# BCK_REVA.net
KiCad netlist of a schematic drawn in Altium Designer
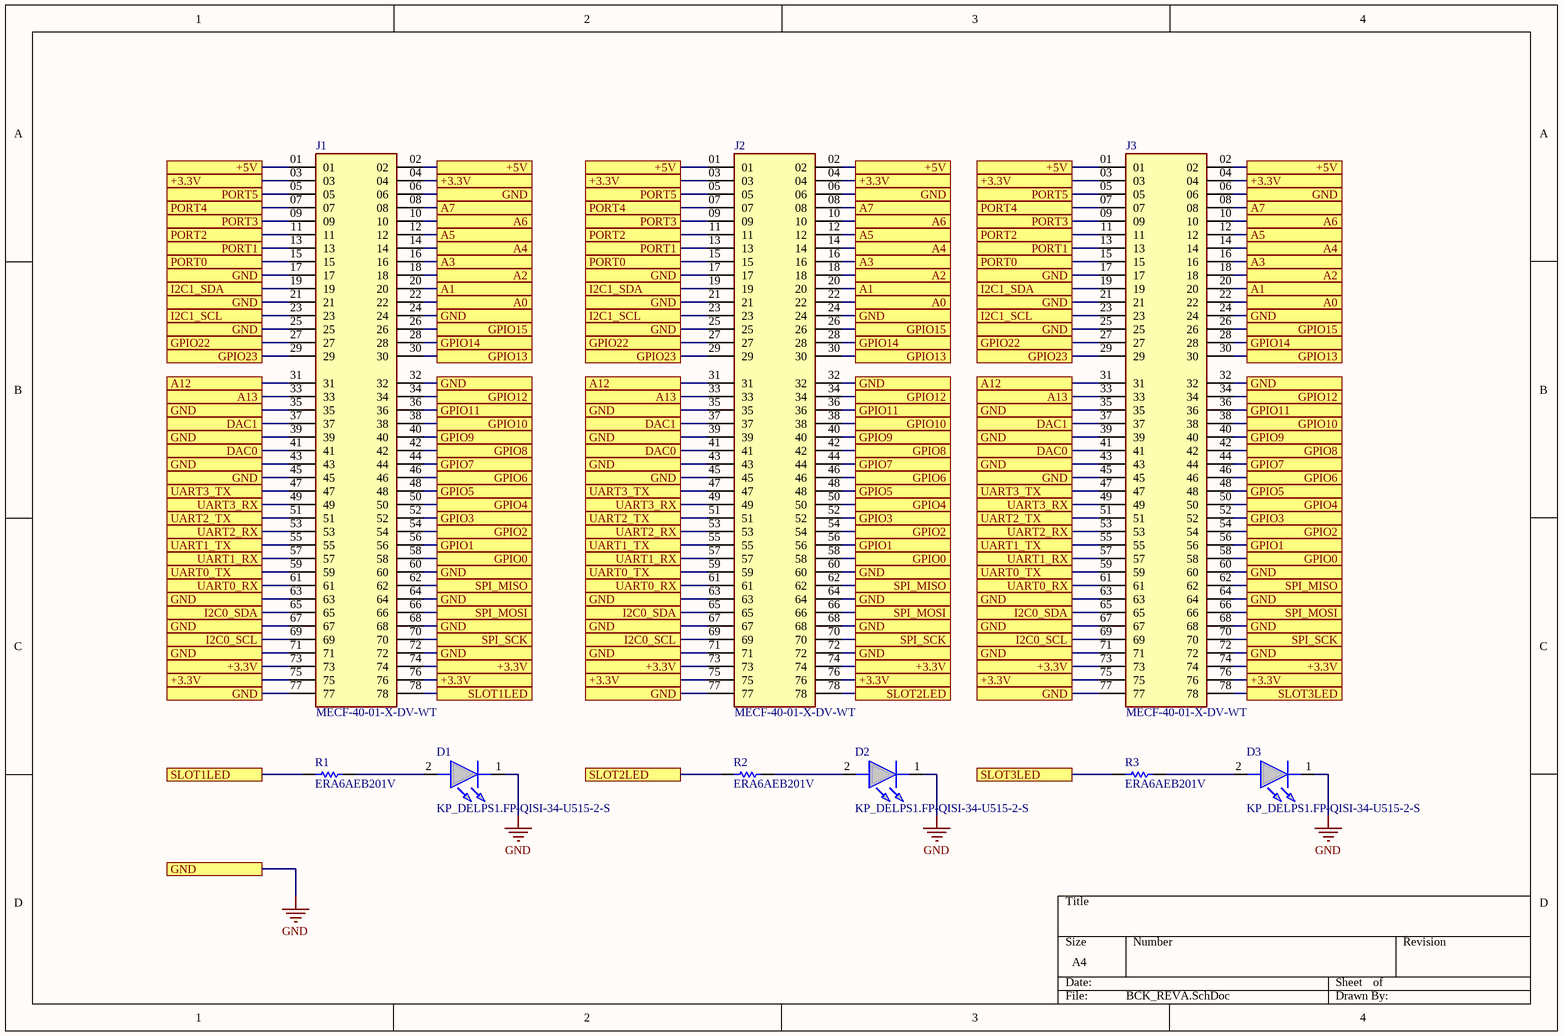
[diagram p0: BCK_REVA.SchDoc]

(export (version "E")
  (design (tool "Eeschema 10.0.6"))
  (components
    (comp (ref "D1")
      (value "KP_DELPS1.FP-QISI-34-U515-2-S")
      (footprint "KPDELPS1FPQISI34U5152S:KPDELPS1FPQISI34U5152S")
      (description "High Power LEDs - Single Color Pure Green TOPLED E1608")
      (fields
        (field (name "MANUFACTURER_PART_NUMBER") "KP DELPS1.FP-QISI-34-U515-2-S")
        (field (name "MOUSER PART NUMBER") "720-KPDELPS1FPA0817")
      )
      (libsource (lib "Backplane_REVA") (part "KP_DELPS1.FP-QISI-34-U515-2-S"))
    )
    (comp (ref "D2")
      (value "KP_DELPS1.FP-QISI-34-U515-2-S")
      (footprint "KPDELPS1FPQISI34U5152S:KPDELPS1FPQISI34U5152S")
      (description "High Power LEDs - Single Color Pure Green TOPLED E1608")
      (fields
        (field (name "MANUFACTURER_PART_NUMBER") "KP DELPS1.FP-QISI-34-U515-2-S")
        (field (name "MOUSER PART NUMBER") "720-KPDELPS1FPA0817")
      )
      (libsource (lib "Backplane_REVA") (part "KP_DELPS1.FP-QISI-34-U515-2-S"))
    )
    (comp (ref "D3")
      (value "KP_DELPS1.FP-QISI-34-U515-2-S")
      (footprint "KPDELPS1FPQISI34U5152S:KPDELPS1FPQISI34U5152S")
      (description "High Power LEDs - Single Color Pure Green TOPLED E1608")
      (fields
        (field (name "MANUFACTURER_PART_NUMBER") "KP DELPS1.FP-QISI-34-U515-2-S")
        (field (name "MOUSER PART NUMBER") "720-KPDELPS1FPA0817")
      )
      (libsource (lib "Backplane_REVA") (part "KP_DELPS1.FP-QISI-34-U515-2-S"))
    )
    (comp (ref "J1")
      (value "MECF-40-01-X-DV-WT")
      (footprint "SAMTEC_MECF-40-01-X-DV-WT:SAMTEC_MECF-40-01-X-DV-WT")
      (description "MECF .050\" EDGE CARD ASSEMBLY")
      (fields (field (name "MF") "Samtec"))
      (libsource (lib "Backplane_REVA") (part "MECF-40-01-X-DV-WT"))
    )
    (comp (ref "J2")
      (value "MECF-40-01-X-DV-WT")
      (footprint "SAMTEC_MECF-40-01-X-DV-WT:SAMTEC_MECF-40-01-X-DV-WT")
      (description "MECF .050\" EDGE CARD ASSEMBLY")
      (fields (field (name "MF") "Samtec"))
      (libsource (lib "Backplane_REVA") (part "MECF-40-01-X-DV-WT"))
    )
    (comp (ref "J3")
      (value "MECF-40-01-X-DV-WT")
      (footprint "SAMTEC_MECF-40-01-X-DV-WT:SAMTEC_MECF-40-01-X-DV-WT")
      (description "MECF .050\" EDGE CARD ASSEMBLY")
      (fields (field (name "MF") "Samtec"))
      (libsource (lib "Backplane_REVA") (part "MECF-40-01-X-DV-WT"))
    )
    (comp (ref "R1")
      (value "ERA6AEB201V")
      (footprint "RESC2013X60X40NL20T25")
      (fields (field (name "MANUFACTURER") "Panasonic"))
      (libsource (lib "Altium Content Vault") (part "RES"))
    )
    (comp (ref "R2")
      (value "ERA6AEB201V")
      (footprint "RESC2013X60X40NL20T25")
      (fields (field (name "MANUFACTURER") "Panasonic"))
      (libsource (lib "Altium Content Vault") (part "RES"))
    )
    (comp (ref "R3")
      (value "ERA6AEB201V")
      (footprint "RESC2013X60X40NL20T25")
      (fields (field (name "MANUFACTURER") "Panasonic"))
      (libsource (lib "Altium Content Vault") (part "RES"))
    )
  )
  (nets
    (net (code "1") (name "/+3.3V") (class "Default")
      (node (ref "J1") (pin "03") (pinfunction "03_03") (pintype "passive"))
      (node (ref "J1") (pin "04") (pinfunction "04_04") (pintype "passive"))
      (node (ref "J1") (pin "73") (pinfunction "73_73") (pintype "passive"))
      (node (ref "J1") (pin "74") (pinfunction "74_74") (pintype "passive"))
      (node (ref "J1") (pin "75") (pinfunction "75_75") (pintype "passive"))
      (node (ref "J1") (pin "76") (pinfunction "76_76") (pintype "passive"))
      (node (ref "J2") (pin "03") (pinfunction "03_03") (pintype "passive"))
      (node (ref "J2") (pin "04") (pinfunction "04_04") (pintype "passive"))
      (node (ref "J2") (pin "73") (pinfunction "73_73") (pintype "passive"))
      (node (ref "J2") (pin "74") (pinfunction "74_74") (pintype "passive"))
      (node (ref "J2") (pin "75") (pinfunction "75_75") (pintype "passive"))
      (node (ref "J2") (pin "76") (pinfunction "76_76") (pintype "passive"))
      (node (ref "J3") (pin "03") (pinfunction "03_03") (pintype "passive"))
      (node (ref "J3") (pin "04") (pinfunction "04_04") (pintype "passive"))
      (node (ref "J3") (pin "73") (pinfunction "73_73") (pintype "passive"))
      (node (ref "J3") (pin "74") (pinfunction "74_74") (pintype "passive"))
      (node (ref "J3") (pin "75") (pinfunction "75_75") (pintype "passive"))
      (node (ref "J3") (pin "76") (pinfunction "76_76") (pintype "passive"))
    )
    (net (code "2") (name "/+5V") (class "Default")
      (node (ref "J1") (pin "01") (pinfunction "01_01") (pintype "passive"))
      (node (ref "J1") (pin "02") (pinfunction "02_02") (pintype "passive"))
      (node (ref "J2") (pin "01") (pinfunction "01_01") (pintype "passive"))
      (node (ref "J2") (pin "02") (pinfunction "02_02") (pintype "passive"))
      (node (ref "J3") (pin "01") (pinfunction "01_01") (pintype "passive"))
      (node (ref "J3") (pin "02") (pinfunction "02_02") (pintype "passive"))
    )
    (net (code "3") (name "/A0") (class "Default")
      (node (ref "J1") (pin "22") (pinfunction "22_22") (pintype "passive"))
      (node (ref "J2") (pin "22") (pinfunction "22_22") (pintype "passive"))
      (node (ref "J3") (pin "22") (pinfunction "22_22") (pintype "passive"))
    )
    (net (code "4") (name "/A1") (class "Default")
      (node (ref "J1") (pin "20") (pinfunction "20_20") (pintype "passive"))
      (node (ref "J2") (pin "20") (pinfunction "20_20") (pintype "passive"))
      (node (ref "J3") (pin "20") (pinfunction "20_20") (pintype "passive"))
    )
    (net (code "5") (name "/A2") (class "Default")
      (node (ref "J1") (pin "18") (pinfunction "18_18") (pintype "passive"))
      (node (ref "J2") (pin "18") (pinfunction "18_18") (pintype "passive"))
      (node (ref "J3") (pin "18") (pinfunction "18_18") (pintype "passive"))
    )
    (net (code "6") (name "/A3") (class "Default")
      (node (ref "J1") (pin "16") (pinfunction "16_16") (pintype "passive"))
      (node (ref "J2") (pin "16") (pinfunction "16_16") (pintype "passive"))
      (node (ref "J3") (pin "16") (pinfunction "16_16") (pintype "passive"))
    )
    (net (code "7") (name "/A4") (class "Default")
      (node (ref "J1") (pin "14") (pinfunction "14_14") (pintype "passive"))
      (node (ref "J2") (pin "14") (pinfunction "14_14") (pintype "passive"))
      (node (ref "J3") (pin "14") (pinfunction "14_14") (pintype "passive"))
    )
    (net (code "8") (name "/A5") (class "Default")
      (node (ref "J1") (pin "12") (pinfunction "12_12") (pintype "passive"))
      (node (ref "J2") (pin "12") (pinfunction "12_12") (pintype "passive"))
      (node (ref "J3") (pin "12") (pinfunction "12_12") (pintype "passive"))
    )
    (net (code "9") (name "/A6") (class "Default")
      (node (ref "J1") (pin "10") (pinfunction "10_10") (pintype "passive"))
      (node (ref "J2") (pin "10") (pinfunction "10_10") (pintype "passive"))
      (node (ref "J3") (pin "10") (pinfunction "10_10") (pintype "passive"))
    )
    (net (code "10") (name "/A7") (class "Default")
      (node (ref "J1") (pin "08") (pinfunction "08_08") (pintype "passive"))
      (node (ref "J2") (pin "08") (pinfunction "08_08") (pintype "passive"))
      (node (ref "J3") (pin "08") (pinfunction "08_08") (pintype "passive"))
    )
    (net (code "11") (name "/A12") (class "Default")
      (node (ref "J1") (pin "31") (pinfunction "31_31") (pintype "passive"))
      (node (ref "J2") (pin "31") (pinfunction "31_31") (pintype "passive"))
      (node (ref "J3") (pin "31") (pinfunction "31_31") (pintype "passive"))
    )
    (net (code "12") (name "/A13") (class "Default")
      (node (ref "J1") (pin "33") (pinfunction "33_33") (pintype "passive"))
      (node (ref "J2") (pin "33") (pinfunction "33_33") (pintype "passive"))
      (node (ref "J3") (pin "33") (pinfunction "33_33") (pintype "passive"))
    )
    (net (code "13") (name "/DAC0") (class "Default")
      (node (ref "J1") (pin "41") (pinfunction "41_41") (pintype "passive"))
      (node (ref "J2") (pin "41") (pinfunction "41_41") (pintype "passive"))
      (node (ref "J3") (pin "41") (pinfunction "41_41") (pintype "passive"))
    )
    (net (code "14") (name "/DAC1") (class "Default")
      (node (ref "J1") (pin "37") (pinfunction "37_37") (pintype "passive"))
      (node (ref "J2") (pin "37") (pinfunction "37_37") (pintype "passive"))
      (node (ref "J3") (pin "37") (pinfunction "37_37") (pintype "passive"))
    )
    (net (code "15") (name "/GPIO0") (class "Default")
      (node (ref "J1") (pin "58") (pinfunction "58_58") (pintype "passive"))
      (node (ref "J2") (pin "58") (pinfunction "58_58") (pintype "passive"))
      (node (ref "J3") (pin "58") (pinfunction "58_58") (pintype "passive"))
    )
    (net (code "16") (name "/GPIO1") (class "Default")
      (node (ref "J1") (pin "56") (pinfunction "56_56") (pintype "passive"))
      (node (ref "J2") (pin "56") (pinfunction "56_56") (pintype "passive"))
      (node (ref "J3") (pin "56") (pinfunction "56_56") (pintype "passive"))
    )
    (net (code "17") (name "/GPIO2") (class "Default")
      (node (ref "J1") (pin "54") (pinfunction "54_54") (pintype "passive"))
      (node (ref "J2") (pin "54") (pinfunction "54_54") (pintype "passive"))
      (node (ref "J3") (pin "54") (pinfunction "54_54") (pintype "passive"))
    )
    (net (code "18") (name "/GPIO3") (class "Default")
      (node (ref "J1") (pin "52") (pinfunction "52_52") (pintype "passive"))
      (node (ref "J2") (pin "52") (pinfunction "52_52") (pintype "passive"))
      (node (ref "J3") (pin "52") (pinfunction "52_52") (pintype "passive"))
    )
    (net (code "19") (name "/GPIO4") (class "Default")
      (node (ref "J1") (pin "50") (pinfunction "50_50") (pintype "passive"))
      (node (ref "J2") (pin "50") (pinfunction "50_50") (pintype "passive"))
      (node (ref "J3") (pin "50") (pinfunction "50_50") (pintype "passive"))
    )
    (net (code "20") (name "/GPIO5") (class "Default")
      (node (ref "J1") (pin "48") (pinfunction "48_48") (pintype "passive"))
      (node (ref "J2") (pin "48") (pinfunction "48_48") (pintype "passive"))
      (node (ref "J3") (pin "48") (pinfunction "48_48") (pintype "passive"))
    )
    (net (code "21") (name "/GPIO6") (class "Default")
      (node (ref "J1") (pin "46") (pinfunction "46_46") (pintype "passive"))
      (node (ref "J2") (pin "46") (pinfunction "46_46") (pintype "passive"))
      (node (ref "J3") (pin "46") (pinfunction "46_46") (pintype "passive"))
    )
    (net (code "22") (name "/GPIO7") (class "Default")
      (node (ref "J1") (pin "44") (pinfunction "44_44") (pintype "passive"))
      (node (ref "J2") (pin "44") (pinfunction "44_44") (pintype "passive"))
      (node (ref "J3") (pin "44") (pinfunction "44_44") (pintype "passive"))
    )
    (net (code "23") (name "/GPIO8") (class "Default")
      (node (ref "J1") (pin "42") (pinfunction "42_42") (pintype "passive"))
      (node (ref "J2") (pin "42") (pinfunction "42_42") (pintype "passive"))
      (node (ref "J3") (pin "42") (pinfunction "42_42") (pintype "passive"))
    )
    (net (code "24") (name "/GPIO9") (class "Default")
      (node (ref "J1") (pin "40") (pinfunction "40_40") (pintype "passive"))
      (node (ref "J2") (pin "40") (pinfunction "40_40") (pintype "passive"))
      (node (ref "J3") (pin "40") (pinfunction "40_40") (pintype "passive"))
    )
    (net (code "25") (name "/GPIO10") (class "Default")
      (node (ref "J1") (pin "38") (pinfunction "38_38") (pintype "passive"))
      (node (ref "J2") (pin "38") (pinfunction "38_38") (pintype "passive"))
      (node (ref "J3") (pin "38") (pinfunction "38_38") (pintype "passive"))
    )
    (net (code "26") (name "/GPIO11") (class "Default")
      (node (ref "J1") (pin "36") (pinfunction "36_36") (pintype "passive"))
      (node (ref "J2") (pin "36") (pinfunction "36_36") (pintype "passive"))
      (node (ref "J3") (pin "36") (pinfunction "36_36") (pintype "passive"))
    )
    (net (code "27") (name "/GPIO12") (class "Default")
      (node (ref "J1") (pin "34") (pinfunction "34_34") (pintype "passive"))
      (node (ref "J2") (pin "34") (pinfunction "34_34") (pintype "passive"))
      (node (ref "J3") (pin "34") (pinfunction "34_34") (pintype "passive"))
    )
    (net (code "28") (name "/GPIO13") (class "Default")
      (node (ref "J1") (pin "30") (pinfunction "30_30") (pintype "passive"))
      (node (ref "J2") (pin "30") (pinfunction "30_30") (pintype "passive"))
      (node (ref "J3") (pin "30") (pinfunction "30_30") (pintype "passive"))
    )
    (net (code "29") (name "/GPIO14") (class "Default")
      (node (ref "J1") (pin "28") (pinfunction "28_28") (pintype "passive"))
      (node (ref "J2") (pin "28") (pinfunction "28_28") (pintype "passive"))
      (node (ref "J3") (pin "28") (pinfunction "28_28") (pintype "passive"))
    )
    (net (code "30") (name "/GPIO15") (class "Default")
      (node (ref "J1") (pin "26") (pinfunction "26_26") (pintype "passive"))
      (node (ref "J2") (pin "26") (pinfunction "26_26") (pintype "passive"))
      (node (ref "J3") (pin "26") (pinfunction "26_26") (pintype "passive"))
    )
    (net (code "31") (name "/GPIO22") (class "Default")
      (node (ref "J1") (pin "27") (pinfunction "27_27") (pintype "passive"))
      (node (ref "J2") (pin "27") (pinfunction "27_27") (pintype "passive"))
      (node (ref "J3") (pin "27") (pinfunction "27_27") (pintype "passive"))
    )
    (net (code "32") (name "/GPIO23") (class "Default")
      (node (ref "J1") (pin "29") (pinfunction "29_29") (pintype "passive"))
      (node (ref "J2") (pin "29") (pinfunction "29_29") (pintype "passive"))
      (node (ref "J3") (pin "29") (pinfunction "29_29") (pintype "passive"))
    )
    (net (code "33") (name "/I2C0_SCL") (class "Default")
      (node (ref "J1") (pin "69") (pinfunction "69_69") (pintype "passive"))
      (node (ref "J2") (pin "69") (pinfunction "69_69") (pintype "passive"))
      (node (ref "J3") (pin "69") (pinfunction "69_69") (pintype "passive"))
    )
    (net (code "34") (name "/I2C0_SDA") (class "Default")
      (node (ref "J1") (pin "65") (pinfunction "65_65") (pintype "passive"))
      (node (ref "J2") (pin "65") (pinfunction "65_65") (pintype "passive"))
      (node (ref "J3") (pin "65") (pinfunction "65_65") (pintype "passive"))
    )
    (net (code "35") (name "/I2C1_SCL") (class "Default")
      (node (ref "J1") (pin "23") (pinfunction "23_23") (pintype "passive"))
      (node (ref "J2") (pin "23") (pinfunction "23_23") (pintype "passive"))
      (node (ref "J3") (pin "23") (pinfunction "23_23") (pintype "passive"))
    )
    (net (code "36") (name "/I2C1_SDA") (class "Default")
      (node (ref "J1") (pin "19") (pinfunction "19_19") (pintype "passive"))
      (node (ref "J2") (pin "19") (pinfunction "19_19") (pintype "passive"))
      (node (ref "J3") (pin "19") (pinfunction "19_19") (pintype "passive"))
    )
    (net (code "37") (name "/PORT0") (class "Default")
      (node (ref "J1") (pin "15") (pinfunction "15_15") (pintype "passive"))
      (node (ref "J2") (pin "15") (pinfunction "15_15") (pintype "passive"))
      (node (ref "J3") (pin "15") (pinfunction "15_15") (pintype "passive"))
    )
    (net (code "38") (name "/PORT1") (class "Default")
      (node (ref "J1") (pin "13") (pinfunction "13_13") (pintype "passive"))
      (node (ref "J2") (pin "13") (pinfunction "13_13") (pintype "passive"))
      (node (ref "J3") (pin "13") (pinfunction "13_13") (pintype "passive"))
    )
    (net (code "39") (name "/PORT2") (class "Default")
      (node (ref "J1") (pin "11") (pinfunction "11_11") (pintype "passive"))
      (node (ref "J2") (pin "11") (pinfunction "11_11") (pintype "passive"))
      (node (ref "J3") (pin "11") (pinfunction "11_11") (pintype "passive"))
    )
    (net (code "40") (name "/PORT3") (class "Default")
      (node (ref "J1") (pin "09") (pinfunction "09_09") (pintype "passive"))
      (node (ref "J2") (pin "09") (pinfunction "09_09") (pintype "passive"))
      (node (ref "J3") (pin "09") (pinfunction "09_09") (pintype "passive"))
    )
    (net (code "41") (name "/PORT4") (class "Default")
      (node (ref "J1") (pin "07") (pinfunction "07_07") (pintype "passive"))
      (node (ref "J2") (pin "07") (pinfunction "07_07") (pintype "passive"))
      (node (ref "J3") (pin "07") (pinfunction "07_07") (pintype "passive"))
    )
    (net (code "42") (name "/PORT5") (class "Default")
      (node (ref "J1") (pin "05") (pinfunction "05_05") (pintype "passive"))
      (node (ref "J2") (pin "05") (pinfunction "05_05") (pintype "passive"))
      (node (ref "J3") (pin "05") (pinfunction "05_05") (pintype "passive"))
    )
    (net (code "43") (name "/SLOT1LED") (class "Default")
      (node (ref "J1") (pin "78") (pinfunction "78_78") (pintype "passive"))
      (node (ref "R1") (pin "1") (pinfunction "1_1") (pintype "passive"))
    )
    (net (code "44") (name "/SLOT2LED") (class "Default")
      (node (ref "J2") (pin "78") (pinfunction "78_78") (pintype "passive"))
      (node (ref "R2") (pin "1") (pinfunction "1_1") (pintype "passive"))
    )
    (net (code "45") (name "/SLOT3LED") (class "Default")
      (node (ref "J3") (pin "78") (pinfunction "78_78") (pintype "passive"))
      (node (ref "R3") (pin "1") (pinfunction "1_1") (pintype "passive"))
    )
    (net (code "46") (name "/SPI_MISO") (class "Default")
      (node (ref "J1") (pin "62") (pinfunction "62_62") (pintype "passive"))
      (node (ref "J2") (pin "62") (pinfunction "62_62") (pintype "passive"))
      (node (ref "J3") (pin "62") (pinfunction "62_62") (pintype "passive"))
    )
    (net (code "47") (name "/SPI_MOSI") (class "Default")
      (node (ref "J1") (pin "66") (pinfunction "66_66") (pintype "passive"))
      (node (ref "J2") (pin "66") (pinfunction "66_66") (pintype "passive"))
      (node (ref "J3") (pin "66") (pinfunction "66_66") (pintype "passive"))
    )
    (net (code "48") (name "/SPI_SCK") (class "Default")
      (node (ref "J1") (pin "70") (pinfunction "70_70") (pintype "passive"))
      (node (ref "J2") (pin "70") (pinfunction "70_70") (pintype "passive"))
      (node (ref "J3") (pin "70") (pinfunction "70_70") (pintype "passive"))
    )
    (net (code "49") (name "/UART0_RX") (class "Default")
      (node (ref "J1") (pin "61") (pinfunction "61_61") (pintype "passive"))
      (node (ref "J2") (pin "61") (pinfunction "61_61") (pintype "passive"))
      (node (ref "J3") (pin "61") (pinfunction "61_61") (pintype "passive"))
    )
    (net (code "50") (name "/UART0_TX") (class "Default")
      (node (ref "J1") (pin "59") (pinfunction "59_59") (pintype "passive"))
      (node (ref "J2") (pin "59") (pinfunction "59_59") (pintype "passive"))
      (node (ref "J3") (pin "59") (pinfunction "59_59") (pintype "passive"))
    )
    (net (code "51") (name "/UART1_RX") (class "Default")
      (node (ref "J1") (pin "57") (pinfunction "57_57") (pintype "passive"))
      (node (ref "J2") (pin "57") (pinfunction "57_57") (pintype "passive"))
      (node (ref "J3") (pin "57") (pinfunction "57_57") (pintype "passive"))
    )
    (net (code "52") (name "/UART1_TX") (class "Default")
      (node (ref "J1") (pin "55") (pinfunction "55_55") (pintype "passive"))
      (node (ref "J2") (pin "55") (pinfunction "55_55") (pintype "passive"))
      (node (ref "J3") (pin "55") (pinfunction "55_55") (pintype "passive"))
    )
    (net (code "53") (name "/UART2_RX") (class "Default")
      (node (ref "J1") (pin "53") (pinfunction "53_53") (pintype "passive"))
      (node (ref "J2") (pin "53") (pinfunction "53_53") (pintype "passive"))
      (node (ref "J3") (pin "53") (pinfunction "53_53") (pintype "passive"))
    )
    (net (code "54") (name "/UART2_TX") (class "Default")
      (node (ref "J1") (pin "51") (pinfunction "51_51") (pintype "passive"))
      (node (ref "J2") (pin "51") (pinfunction "51_51") (pintype "passive"))
      (node (ref "J3") (pin "51") (pinfunction "51_51") (pintype "passive"))
    )
    (net (code "55") (name "/UART3_RX") (class "Default")
      (node (ref "J1") (pin "49") (pinfunction "49_49") (pintype "passive"))
      (node (ref "J2") (pin "49") (pinfunction "49_49") (pintype "passive"))
      (node (ref "J3") (pin "49") (pinfunction "49_49") (pintype "passive"))
    )
    (net (code "56") (name "/UART3_TX") (class "Default")
      (node (ref "J1") (pin "47") (pinfunction "47_47") (pintype "passive"))
      (node (ref "J2") (pin "47") (pinfunction "47_47") (pintype "passive"))
      (node (ref "J3") (pin "47") (pinfunction "47_47") (pintype "passive"))
    )
    (net (code "57") (name "GND") (class "Default")
      (node (ref "D1") (pin "1") (pinfunction "K_1") (pintype "passive"))
      (node (ref "D2") (pin "1") (pinfunction "K_1") (pintype "passive"))
      (node (ref "D3") (pin "1") (pinfunction "K_1") (pintype "passive"))
      (node (ref "J1") (pin "06") (pinfunction "06_06") (pintype "passive"))
      (node (ref "J1") (pin "17") (pinfunction "17_17") (pintype "passive"))
      (node (ref "J1") (pin "21") (pinfunction "21_21") (pintype "passive"))
      (node (ref "J1") (pin "24") (pinfunction "24_24") (pintype "passive"))
      (node (ref "J1") (pin "25") (pinfunction "25_25") (pintype "passive"))
      (node (ref "J1") (pin "32") (pinfunction "32_32") (pintype "passive"))
      (node (ref "J1") (pin "35") (pinfunction "35_35") (pintype "passive"))
      (node (ref "J1") (pin "39") (pinfunction "39_39") (pintype "passive"))
      (node (ref "J1") (pin "43") (pinfunction "43_43") (pintype "passive"))
      (node (ref "J1") (pin "45") (pinfunction "45_45") (pintype "passive"))
      (node (ref "J1") (pin "60") (pinfunction "60_60") (pintype "passive"))
      (node (ref "J1") (pin "63") (pinfunction "63_63") (pintype "passive"))
      (node (ref "J1") (pin "64") (pinfunction "64_64") (pintype "passive"))
      (node (ref "J1") (pin "67") (pinfunction "67_67") (pintype "passive"))
      (node (ref "J1") (pin "68") (pinfunction "68_68") (pintype "passive"))
      (node (ref "J1") (pin "71") (pinfunction "71_71") (pintype "passive"))
      (node (ref "J1") (pin "72") (pinfunction "72_72") (pintype "passive"))
      (node (ref "J1") (pin "77") (pinfunction "77_77") (pintype "passive"))
      (node (ref "J2") (pin "06") (pinfunction "06_06") (pintype "passive"))
      (node (ref "J2") (pin "17") (pinfunction "17_17") (pintype "passive"))
      (node (ref "J2") (pin "21") (pinfunction "21_21") (pintype "passive"))
      (node (ref "J2") (pin "24") (pinfunction "24_24") (pintype "passive"))
      (node (ref "J2") (pin "25") (pinfunction "25_25") (pintype "passive"))
      (node (ref "J2") (pin "32") (pinfunction "32_32") (pintype "passive"))
      (node (ref "J2") (pin "35") (pinfunction "35_35") (pintype "passive"))
      (node (ref "J2") (pin "39") (pinfunction "39_39") (pintype "passive"))
      (node (ref "J2") (pin "43") (pinfunction "43_43") (pintype "passive"))
      (node (ref "J2") (pin "45") (pinfunction "45_45") (pintype "passive"))
      (node (ref "J2") (pin "60") (pinfunction "60_60") (pintype "passive"))
      (node (ref "J2") (pin "63") (pinfunction "63_63") (pintype "passive"))
      (node (ref "J2") (pin "64") (pinfunction "64_64") (pintype "passive"))
      (node (ref "J2") (pin "67") (pinfunction "67_67") (pintype "passive"))
      (node (ref "J2") (pin "68") (pinfunction "68_68") (pintype "passive"))
      (node (ref "J2") (pin "71") (pinfunction "71_71") (pintype "passive"))
      (node (ref "J2") (pin "72") (pinfunction "72_72") (pintype "passive"))
      (node (ref "J2") (pin "77") (pinfunction "77_77") (pintype "passive"))
      (node (ref "J3") (pin "06") (pinfunction "06_06") (pintype "passive"))
      (node (ref "J3") (pin "17") (pinfunction "17_17") (pintype "passive"))
      (node (ref "J3") (pin "21") (pinfunction "21_21") (pintype "passive"))
      (node (ref "J3") (pin "24") (pinfunction "24_24") (pintype "passive"))
      (node (ref "J3") (pin "25") (pinfunction "25_25") (pintype "passive"))
      (node (ref "J3") (pin "32") (pinfunction "32_32") (pintype "passive"))
      (node (ref "J3") (pin "35") (pinfunction "35_35") (pintype "passive"))
      (node (ref "J3") (pin "39") (pinfunction "39_39") (pintype "passive"))
      (node (ref "J3") (pin "43") (pinfunction "43_43") (pintype "passive"))
      (node (ref "J3") (pin "45") (pinfunction "45_45") (pintype "passive"))
      (node (ref "J3") (pin "60") (pinfunction "60_60") (pintype "passive"))
      (node (ref "J3") (pin "63") (pinfunction "63_63") (pintype "passive"))
      (node (ref "J3") (pin "64") (pinfunction "64_64") (pintype "passive"))
      (node (ref "J3") (pin "67") (pinfunction "67_67") (pintype "passive"))
      (node (ref "J3") (pin "68") (pinfunction "68_68") (pintype "passive"))
      (node (ref "J3") (pin "71") (pinfunction "71_71") (pintype "passive"))
      (node (ref "J3") (pin "72") (pinfunction "72_72") (pintype "passive"))
      (node (ref "J3") (pin "77") (pinfunction "77_77") (pintype "passive"))
    )
    (net (code "58") (name "Net-(D1-A)") (class "Default")
      (node (ref "D1") (pin "2") (pinfunction "A_2") (pintype "passive"))
      (node (ref "R1") (pin "2") (pinfunction "2_2") (pintype "passive"))
    )
    (net (code "59") (name "Net-(D2-A)") (class "Default")
      (node (ref "D2") (pin "2") (pinfunction "A_2") (pintype "passive"))
      (node (ref "R2") (pin "2") (pinfunction "2_2") (pintype "passive"))
    )
    (net (code "60") (name "Net-(D3-A)") (class "Default")
      (node (ref "D3") (pin "2") (pinfunction "A_2") (pintype "passive"))
      (node (ref "R3") (pin "2") (pinfunction "2_2") (pintype "passive"))
    )
  )
)
